# digital-encoder.net
KiCad netlist of a schematic drawn in Altium Designer
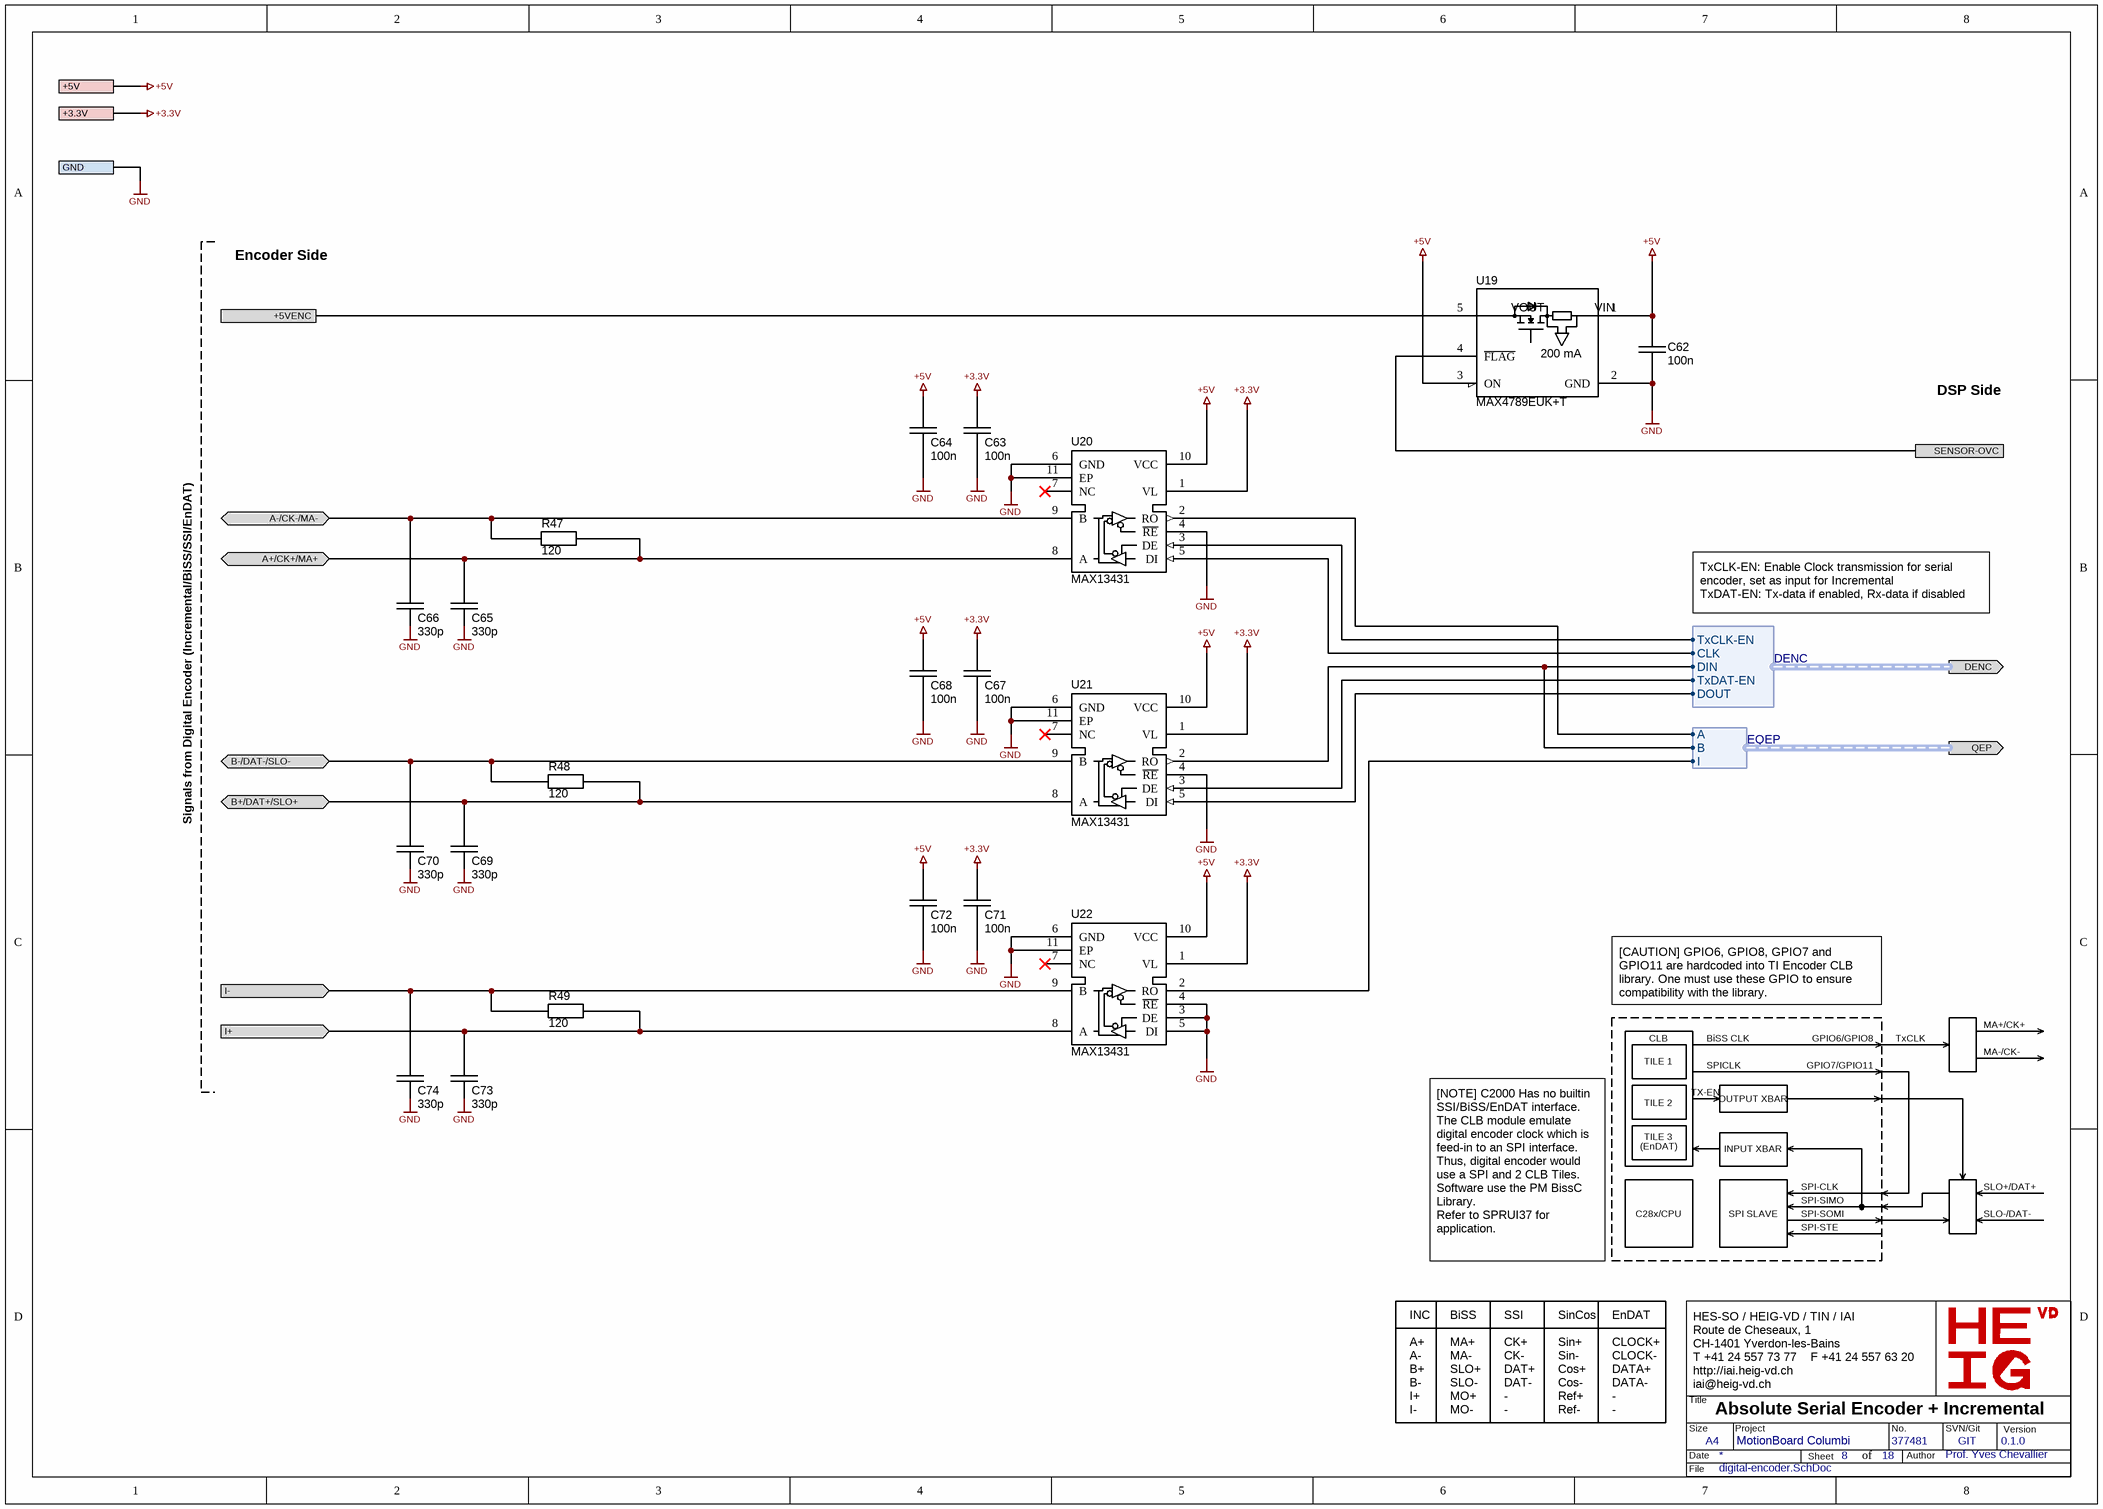
[diagram p0: digital-encoder.SchDoc]

(export (version "E")
  (design (tool "Eeschema 10.0.6"))
  (components
    (comp (ref "C62")
      (value "100n")
      (footprint "SM/C0402")
      (description "100 nF ±10% 25V Ceramic Capacitor X5R 0402 (1005 Metric)")
      (fields (field (name "VOLTAGE") "25V"))
      (libsource (lib "motionboard") (part "CAP CER 100NF 25V X5R 0402"))
    )
    (comp (ref "C63")
      (value "100n")
      (footprint "SM/C0402")
      (description "100 nF ±10% 25V Ceramic Capacitor X5R 0402 (1005 Metric)")
      (fields (field (name "VOLTAGE") "25V"))
      (libsource (lib "motionboard") (part "CAP CER 100NF 25V X5R 0402"))
    )
    (comp (ref "C64")
      (value "100n")
      (footprint "SM/C0402")
      (description "100 nF ±10% 25V Ceramic Capacitor X5R 0402 (1005 Metric)")
      (fields (field (name "VOLTAGE") "25V"))
      (libsource (lib "motionboard") (part "CAP CER 100NF 25V X5R 0402"))
    )
    (comp (ref "C65")
      (value "330p")
      (footprint "SM/C0402")
      (description "330 pF ±5% 50V Ceramic Capacitor C0G, NP0 0402 (1005 Metric)")
      (fields (field (name "VOLTAGE") "50V"))
      (libsource (lib "motionboard") (part "CAP CER 330PF 50V C0G/NP0 0402"))
    )
    (comp (ref "C66")
      (value "330p")
      (footprint "SM/C0402")
      (description "330 pF ±5% 50V Ceramic Capacitor C0G, NP0 0402 (1005 Metric)")
      (fields (field (name "VOLTAGE") "50V"))
      (libsource (lib "motionboard") (part "CAP CER 330PF 50V C0G/NP0 0402"))
    )
    (comp (ref "C67")
      (value "100n")
      (footprint "SM/C0402")
      (description "100 nF ±10% 25V Ceramic Capacitor X5R 0402 (1005 Metric)")
      (fields (field (name "VOLTAGE") "25V"))
      (libsource (lib "motionboard") (part "CAP CER 100NF 25V X5R 0402"))
    )
    (comp (ref "C68")
      (value "100n")
      (footprint "SM/C0402")
      (description "100 nF ±10% 25V Ceramic Capacitor X5R 0402 (1005 Metric)")
      (fields (field (name "VOLTAGE") "25V"))
      (libsource (lib "motionboard") (part "CAP CER 100NF 25V X5R 0402"))
    )
    (comp (ref "C69")
      (value "330p")
      (footprint "SM/C0402")
      (description "330 pF ±5% 50V Ceramic Capacitor C0G, NP0 0402 (1005 Metric)")
      (fields (field (name "VOLTAGE") "50V"))
      (libsource (lib "motionboard") (part "CAP CER 330PF 50V C0G/NP0 0402"))
    )
    (comp (ref "C70")
      (value "330p")
      (footprint "SM/C0402")
      (description "330 pF ±5% 50V Ceramic Capacitor C0G, NP0 0402 (1005 Metric)")
      (fields (field (name "VOLTAGE") "50V"))
      (libsource (lib "motionboard") (part "CAP CER 330PF 50V C0G/NP0 0402"))
    )
    (comp (ref "C71")
      (value "100n")
      (footprint "SM/C0402")
      (description "100 nF ±10% 25V Ceramic Capacitor X5R 0402 (1005 Metric)")
      (fields (field (name "VOLTAGE") "25V"))
      (libsource (lib "motionboard") (part "CAP CER 100NF 25V X5R 0402"))
    )
    (comp (ref "C72")
      (value "100n")
      (footprint "SM/C0402")
      (description "100 nF ±10% 25V Ceramic Capacitor X5R 0402 (1005 Metric)")
      (fields (field (name "VOLTAGE") "25V"))
      (libsource (lib "motionboard") (part "CAP CER 100NF 25V X5R 0402"))
    )
    (comp (ref "C73")
      (value "330p")
      (footprint "SM/C0402")
      (description "330 pF ±5% 50V Ceramic Capacitor C0G, NP0 0402 (1005 Metric)")
      (fields (field (name "VOLTAGE") "50V"))
      (libsource (lib "motionboard") (part "CAP CER 330PF 50V C0G/NP0 0402"))
    )
    (comp (ref "C74")
      (value "330p")
      (footprint "SM/C0402")
      (description "330 pF ±5% 50V Ceramic Capacitor C0G, NP0 0402 (1005 Metric)")
      (fields (field (name "VOLTAGE") "50V"))
      (libsource (lib "motionboard") (part "CAP CER 330PF 50V C0G/NP0 0402"))
    )
    (comp (ref "R47")
      (value "120")
      (footprint "SM/R0402")
      (description "120 Ohms ±1% 0.063W, 1/16W Chip Resistor 0402 (1005 Metric) Moisture Resistant Thick Film")
      (libsource (lib "motionboard") (part "RES 120 OHM 1% 1/16W 0402"))
    )
    (comp (ref "R48")
      (value "120")
      (footprint "SM/R0402")
      (description "120 Ohms ±1% 0.063W, 1/16W Chip Resistor 0402 (1005 Metric) Moisture Resistant Thick Film")
      (libsource (lib "motionboard") (part "RES 120 OHM 1% 1/16W 0402"))
    )
    (comp (ref "R49")
      (value "120")
      (footprint "SM/R0402")
      (description "120 Ohms ±1% 0.063W, 1/16W Chip Resistor 0402 (1005 Metric) Moisture Resistant Thick Film")
      (libsource (lib "motionboard") (part "RES 120 OHM 1% 1/16W 0402"))
    )
    (comp (ref "U19")
      (value "MAX4789EUK+T")
      (footprint "SOT23-5")
      (description "Current Limiting Regulator 200mA SOT-23-5")
      (fields (field (name "VOLTAGE") "2.3..5.5V"))
      (libsource (lib "motionboard") (part "MAX4789"))
    )
    (comp (ref "U20")
      (value "MAX13431")
      (footprint "DFN10_3x3MC_MCH-M")
      (description "1/1 Transceiver Half RS422, RS485 10-TDFN (3x3)")
      (libsource (lib "motionboard") (part "MAX13431"))
    )
    (comp (ref "U21")
      (value "MAX13431")
      (footprint "DFN10_3x3MC_MCH-M")
      (description "1/1 Transceiver Half RS422, RS485 10-TDFN (3x3)")
      (libsource (lib "motionboard") (part "MAX13431"))
    )
    (comp (ref "U22")
      (value "MAX13431")
      (footprint "DFN10_3x3MC_MCH-M")
      (description "1/1 Transceiver Half RS422, RS485 10-TDFN (3x3)")
      (libsource (lib "motionboard") (part "MAX13431"))
    )
  )
  (nets
    (net (code "3") (name "+3.3V") (class "Default")
      (node (ref "C63") (pin "2") (pintype "passive"))
      (node (ref "C67") (pin "2") (pintype "passive"))
      (node (ref "C71") (pin "2") (pintype "passive"))
      (node (ref "U20") (pin "1") (pinfunction "VL_1") (pintype "passive"))
      (node (ref "U21") (pin "1") (pinfunction "VL_1") (pintype "passive"))
      (node (ref "U22") (pin "1") (pinfunction "VL_1") (pintype "passive"))
    )
    (net (code "4") (name "+5V") (class "Default")
      (node (ref "C62") (pin "1") (pintype "passive"))
      (node (ref "C64") (pin "2") (pintype "passive"))
      (node (ref "C68") (pin "2") (pintype "passive"))
      (node (ref "C72") (pin "2") (pintype "passive"))
      (node (ref "U19") (pin "1") (pinfunction "VIN_1") (pintype "passive"))
      (node (ref "U19") (pin "3") (pinfunction "ON_3") (pintype "passive"))
      (node (ref "U20") (pin "10") (pinfunction "VCC_10") (pintype "passive"))
      (node (ref "U21") (pin "10") (pinfunction "VCC_10") (pintype "passive"))
      (node (ref "U22") (pin "10") (pinfunction "VCC_10") (pintype "passive"))
    )
    (net (code "5") (name "/+5VENC") (class "Default")
      (node (ref "U19") (pin "5") (pinfunction "VOUT_5") (pintype "passive"))
    )
    (net (code "6") (name "/A") (class "Default")
      (node (ref "U20") (pin "2") (pinfunction "RO_2") (pintype "output"))
    )
    (net (code "7") (name "/A+{slash}CK+{slash}MA+") (class "Default")
      (node (ref "C65") (pin "1") (pintype "passive"))
      (node (ref "R47") (pin "1") (pintype "passive"))
      (node (ref "U20") (pin "8") (pinfunction "A_8") (pintype "passive"))
    )
    (net (code "8") (name "/A-{slash}CK-{slash}MA-") (class "Default")
      (node (ref "C66") (pin "1") (pintype "passive"))
      (node (ref "R47") (pin "2") (pintype "passive"))
      (node (ref "U20") (pin "9") (pinfunction "B_9") (pintype "passive"))
    )
    (net (code "9") (name "/B") (class "Default")
      (node (ref "U21") (pin "2") (pinfunction "RO_2") (pintype "output"))
    )
    (net (code "10") (name "/B+{slash}DAT+{slash}SLO+") (class "Default")
      (node (ref "C69") (pin "1") (pintype "passive"))
      (node (ref "R48") (pin "1") (pintype "passive"))
      (node (ref "U21") (pin "8") (pinfunction "A_8") (pintype "passive"))
    )
    (net (code "11") (name "/B-{slash}DAT-{slash}SLO-") (class "Default")
      (node (ref "C70") (pin "1") (pintype "passive"))
      (node (ref "R48") (pin "2") (pintype "passive"))
      (node (ref "U21") (pin "9") (pinfunction "B_9") (pintype "passive"))
    )
    (net (code "12") (name "/CLK") (class "Default")
      (node (ref "U20") (pin "5") (pinfunction "DI_5") (pintype "input"))
    )
    (net (code "13") (name "/DOUT") (class "Default")
      (node (ref "U21") (pin "5") (pinfunction "DI_5") (pintype "input"))
    )
    (net (code "14") (name "/I") (class "Default")
      (node (ref "U22") (pin "2") (pinfunction "RO_2") (pintype "output"))
    )
    (net (code "15") (name "/I+") (class "Default")
      (node (ref "C73") (pin "1") (pintype "passive"))
      (node (ref "R49") (pin "1") (pintype "passive"))
      (node (ref "U22") (pin "8") (pinfunction "A_8") (pintype "passive"))
    )
    (net (code "16") (name "/I-") (class "Default")
      (node (ref "C74") (pin "1") (pintype "passive"))
      (node (ref "R49") (pin "2") (pintype "passive"))
      (node (ref "U22") (pin "9") (pinfunction "B_9") (pintype "passive"))
    )
    (net (code "17") (name "/SENSOR-OVC") (class "Default")
      (node (ref "U19") (pin "4") (pinfunction "~{FLAG}_4") (pintype "passive"))
    )
    (net (code "18") (name "/TxCLK-EN") (class "Default")
      (node (ref "U20") (pin "3") (pinfunction "DE_3") (pintype "input"))
    )
    (net (code "19") (name "/TxDAT-EN") (class "Default")
      (node (ref "U21") (pin "3") (pinfunction "DE_3") (pintype "input"))
    )
    (net (code "22") (name "GND") (class "Default")
      (node (ref "C62") (pin "2") (pintype "passive"))
      (node (ref "C63") (pin "1") (pintype "passive"))
      (node (ref "C64") (pin "1") (pintype "passive"))
      (node (ref "C65") (pin "2") (pintype "passive"))
      (node (ref "C66") (pin "2") (pintype "passive"))
      (node (ref "C67") (pin "1") (pintype "passive"))
      (node (ref "C68") (pin "1") (pintype "passive"))
      (node (ref "C69") (pin "2") (pintype "passive"))
      (node (ref "C70") (pin "2") (pintype "passive"))
      (node (ref "C71") (pin "1") (pintype "passive"))
      (node (ref "C72") (pin "1") (pintype "passive"))
      (node (ref "C73") (pin "2") (pintype "passive"))
      (node (ref "C74") (pin "2") (pintype "passive"))
      (node (ref "U19") (pin "2") (pinfunction "GND_2") (pintype "passive"))
      (node (ref "U20") (pin "11") (pinfunction "EP_11") (pintype "passive"))
      (node (ref "U20") (pin "4") (pinfunction "~{RE}_4") (pintype "passive"))
      (node (ref "U20") (pin "6") (pinfunction "GND_6") (pintype "passive"))
      (node (ref "U21") (pin "11") (pinfunction "EP_11") (pintype "passive"))
      (node (ref "U21") (pin "4") (pinfunction "~{RE}_4") (pintype "passive"))
      (node (ref "U21") (pin "6") (pinfunction "GND_6") (pintype "passive"))
      (node (ref "U22") (pin "11") (pinfunction "EP_11") (pintype "passive"))
      (node (ref "U22") (pin "3") (pinfunction "DE_3") (pintype "input"))
      (node (ref "U22") (pin "4") (pinfunction "~{RE}_4") (pintype "passive"))
      (node (ref "U22") (pin "5") (pinfunction "DI_5") (pintype "input"))
      (node (ref "U22") (pin "6") (pinfunction "GND_6") (pintype "passive"))
    )
    (net (code "23") (name "unconnected-(U20-NC-Pad7)") (class "Default")
      (node (ref "U20") (pin "7") (pinfunction "NC_7") (pintype "passive+no_connect"))
    )
    (net (code "24") (name "unconnected-(U21-NC-Pad7)") (class "Default")
      (node (ref "U21") (pin "7") (pinfunction "NC_7") (pintype "passive+no_connect"))
    )
    (net (code "25") (name "unconnected-(U22-NC-Pad7)") (class "Default")
      (node (ref "U22") (pin "7") (pinfunction "NC_7") (pintype "passive+no_connect"))
    )
  )
)
